# LiFePo4_Charger_Single_to_Chain_2_1_SMD_.net
KiCad netlist of a schematic drawn in EAGLE
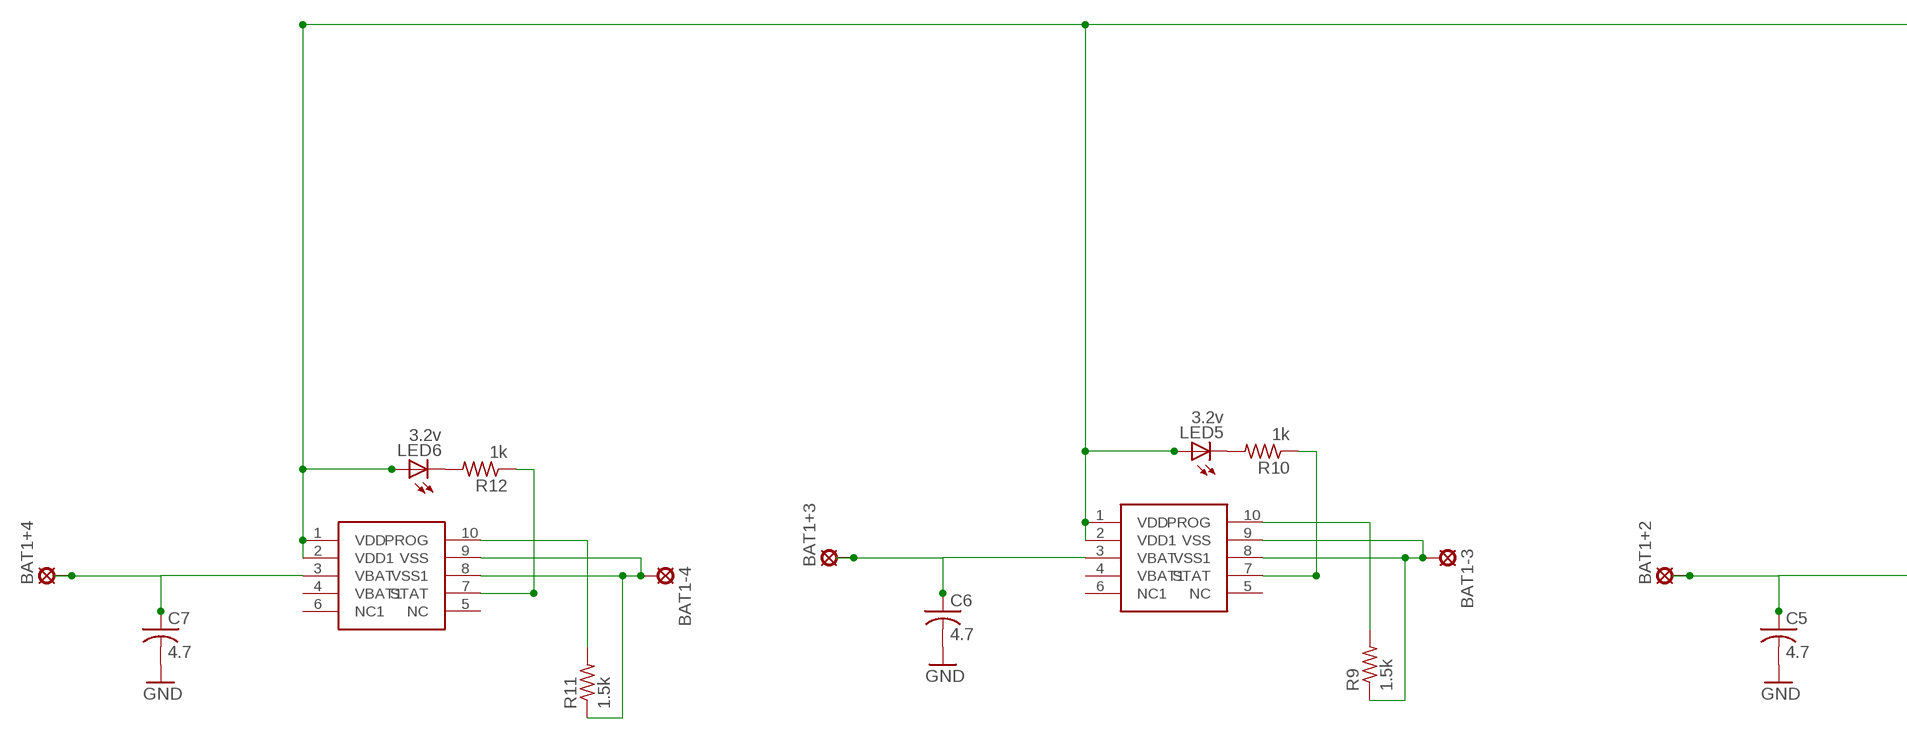
[diagram p0: schematic, sheet 1, part 1 of 2]
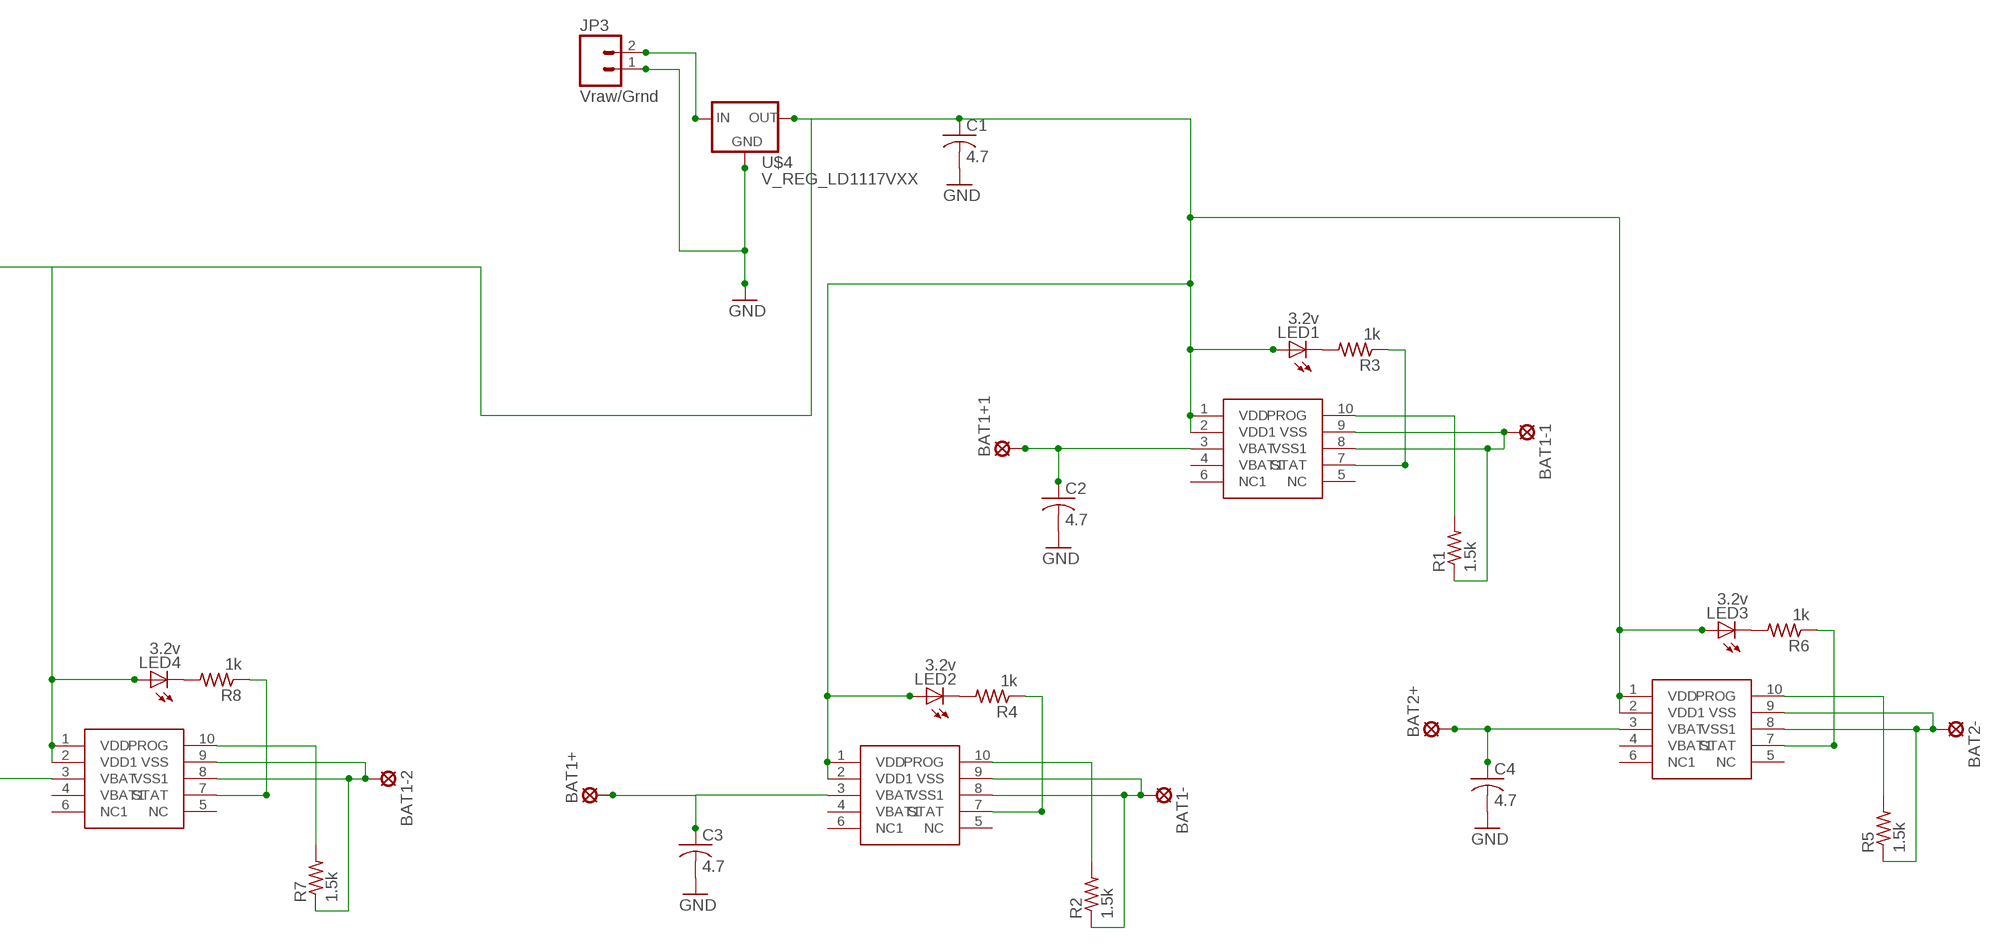
[diagram p1: schematic, sheet 1, part 2 of 2]

(export (version "E")
  (design (tool "Eeschema 10.0.6"))
  (components
    (comp (ref "BAT1+")
      (value "SE14")
      (footprint "eagle-import:SE14")
      (libsource (lib "eagle-import") (part "SE14"))
    )
    (comp (ref "BAT1+1")
      (value "SE14")
      (footprint "eagle-import:SE14")
      (libsource (lib "eagle-import") (part "SE14"))
    )
    (comp (ref "BAT1+2")
      (value "SE14")
      (footprint "eagle-import:SE14")
      (libsource (lib "eagle-import") (part "SE14"))
    )
    (comp (ref "BAT1+3")
      (value "SE14")
      (footprint "eagle-import:SE14")
      (libsource (lib "eagle-import") (part "SE14"))
    )
    (comp (ref "BAT1+4")
      (value "SE14")
      (footprint "eagle-import:SE14")
      (libsource (lib "eagle-import") (part "SE14"))
    )
    (comp (ref "BAT1-")
      (value "SE14")
      (footprint "eagle-import:SE14")
      (libsource (lib "eagle-import") (part "SE14"))
    )
    (comp (ref "BAT1-1")
      (value "SE14")
      (footprint "eagle-import:SE14")
      (libsource (lib "eagle-import") (part "SE14"))
    )
    (comp (ref "BAT1-2")
      (value "SE14")
      (footprint "eagle-import:SE14")
      (libsource (lib "eagle-import") (part "SE14"))
    )
    (comp (ref "BAT1-3")
      (value "SE14")
      (footprint "eagle-import:SE14")
      (libsource (lib "eagle-import") (part "SE14"))
    )
    (comp (ref "BAT1-4")
      (value "SE14")
      (footprint "eagle-import:SE14")
      (libsource (lib "eagle-import") (part "SE14"))
    )
    (comp (ref "BAT2+")
      (value "SE14")
      (footprint "eagle-import:SE14")
      (libsource (lib "eagle-import") (part "SE14"))
    )
    (comp (ref "BAT2-")
      (value "SE14")
      (footprint "eagle-import:SE14")
      (libsource (lib "eagle-import") (part "SE14"))
    )
    (comp (ref "C1")
      (value "4.7")
      (footprint "eagle-import:C0805")
      (libsource (lib "eagle-import") (part "C-USC0805"))
    )
    (comp (ref "C2")
      (value "4.7")
      (footprint "eagle-import:C0805")
      (libsource (lib "eagle-import") (part "C-USC0805"))
    )
    (comp (ref "C3")
      (value "4.7")
      (footprint "eagle-import:C0805")
      (libsource (lib "eagle-import") (part "C-USC0805"))
    )
    (comp (ref "C4")
      (value "4.7")
      (footprint "eagle-import:C0805")
      (libsource (lib "eagle-import") (part "C-USC0805"))
    )
    (comp (ref "C5")
      (value "4.7")
      (footprint "eagle-import:C0805")
      (libsource (lib "eagle-import") (part "C-USC0805"))
    )
    (comp (ref "C6")
      (value "4.7")
      (footprint "eagle-import:C0805")
      (libsource (lib "eagle-import") (part "C-USC0805"))
    )
    (comp (ref "C7")
      (value "4.7")
      (footprint "eagle-import:C0805")
      (libsource (lib "eagle-import") (part "C-USC0805"))
    )
    (comp (ref "JP3")
      (value "Vraw/Grnd")
      (footprint "eagle-import:1X02")
      (libsource (lib "eagle-import") (part "M02PTH"))
    )
    (comp (ref "LED1")
      (value "3.2v")
      (footprint "eagle-import:SML0603")
      (libsource (lib "eagle-import") (part "LEDSML0603"))
    )
    (comp (ref "LED2")
      (value "3.2v")
      (footprint "eagle-import:SML0603")
      (libsource (lib "eagle-import") (part "LEDSML0603"))
    )
    (comp (ref "LED3")
      (value "3.2v")
      (footprint "eagle-import:SML0603")
      (libsource (lib "eagle-import") (part "LEDSML0603"))
    )
    (comp (ref "LED4")
      (value "3.2v")
      (footprint "eagle-import:SML0603")
      (libsource (lib "eagle-import") (part "LEDSML0603"))
    )
    (comp (ref "LED5")
      (value "3.2v")
      (footprint "eagle-import:SML0603")
      (libsource (lib "eagle-import") (part "LEDSML0603"))
    )
    (comp (ref "LED6")
      (value "3.2v")
      (footprint "eagle-import:SML0603")
      (libsource (lib "eagle-import") (part "LEDSML0603"))
    )
    (comp (ref "R1")
      (value "1.5k")
      (footprint "eagle-import:R0805")
      (libsource (lib "eagle-import") (part "R-US_R0805"))
    )
    (comp (ref "R2")
      (value "1.5k")
      (footprint "eagle-import:R0805")
      (libsource (lib "eagle-import") (part "R-US_R0805"))
    )
    (comp (ref "R3")
      (value "1k")
      (footprint "eagle-import:R0805")
      (libsource (lib "eagle-import") (part "R-US_R0805"))
    )
    (comp (ref "R4")
      (value "1k")
      (footprint "eagle-import:R0805")
      (libsource (lib "eagle-import") (part "R-US_R0805"))
    )
    (comp (ref "R5")
      (value "1.5k")
      (footprint "eagle-import:R0805")
      (libsource (lib "eagle-import") (part "R-US_R0805"))
    )
    (comp (ref "R6")
      (value "1k")
      (footprint "eagle-import:R0805")
      (libsource (lib "eagle-import") (part "R-US_R0805"))
    )
    (comp (ref "R7")
      (value "1.5k")
      (footprint "eagle-import:R0805")
      (libsource (lib "eagle-import") (part "R-US_R0805"))
    )
    (comp (ref "R8")
      (value "1k")
      (footprint "eagle-import:R0805")
      (libsource (lib "eagle-import") (part "R-US_R0805"))
    )
    (comp (ref "R9")
      (value "1.5k")
      (footprint "eagle-import:R0805")
      (libsource (lib "eagle-import") (part "R-US_R0805"))
    )
    (comp (ref "R10")
      (value "1k")
      (footprint "eagle-import:R0805")
      (libsource (lib "eagle-import") (part "R-US_R0805"))
    )
    (comp (ref "R11")
      (value "1.5k")
      (footprint "eagle-import:R0805")
      (libsource (lib "eagle-import") (part "R-US_R0805"))
    )
    (comp (ref "R12")
      (value "1k")
      (footprint "eagle-import:R0805")
      (libsource (lib "eagle-import") (part "R-US_R0805"))
    )
    (comp (ref "U$1")
      (value "MCP73123/223")
      (footprint "eagle-import:MCP73123_223")
      (libsource (lib "eagle-import") (part "MCP73123/223"))
    )
    (comp (ref "U$2")
      (value "MCP73123/223")
      (footprint "eagle-import:MCP73123_223")
      (libsource (lib "eagle-import") (part "MCP73123/223"))
    )
    (comp (ref "U$3")
      (value "MCP73123/223")
      (footprint "eagle-import:MCP73123_223")
      (libsource (lib "eagle-import") (part "MCP73123/223"))
    )
    (comp (ref "U$4")
      (value "V_REG_LD1117VXX")
      (footprint "eagle-import:78XXL")
      (libsource (lib "eagle-import") (part "V_REG_LD1117VXX"))
    )
    (comp (ref "U$5")
      (value "MCP73123/223")
      (footprint "eagle-import:MCP73123_223")
      (libsource (lib "eagle-import") (part "MCP73123/223"))
    )
    (comp (ref "U$6")
      (value "MCP73123/223")
      (footprint "eagle-import:MCP73123_223")
      (libsource (lib "eagle-import") (part "MCP73123/223"))
    )
    (comp (ref "U$8")
      (value "MCP73123/223")
      (footprint "eagle-import:MCP73123_223")
      (libsource (lib "eagle-import") (part "MCP73123/223"))
    )
  )
  (nets
    (net (code "1") (name "GND") (class "Default")
      (node (ref "C1") (pin "2") (pinfunction "2_2") (pintype "passive"))
      (node (ref "C2") (pin "2") (pinfunction "2_2") (pintype "passive"))
      (node (ref "C3") (pin "2") (pinfunction "2_2") (pintype "passive"))
      (node (ref "C4") (pin "2") (pinfunction "2_2") (pintype "passive"))
      (node (ref "C5") (pin "2") (pinfunction "2_2") (pintype "passive"))
      (node (ref "C6") (pin "2") (pinfunction "2_2") (pintype "passive"))
      (node (ref "C7") (pin "2") (pinfunction "2_2") (pintype "passive"))
      (node (ref "JP3") (pin "1") (pinfunction "1_1") (pintype "passive"))
      (node (ref "U$4") (pin "IN") (pinfunction "GND_IN") (pintype "input"))
    )
    (net (code "2") (name "Net-(LED1-PadC)") (class "Default")
      (node (ref "LED1") (pin "C") (pinfunction "C_C") (pintype "passive"))
      (node (ref "R3") (pin "2") (pinfunction "2_2") (pintype "passive"))
    )
    (net (code "3") (name "Net-(LED2-PadC)") (class "Default")
      (node (ref "LED2") (pin "C") (pinfunction "C_C") (pintype "passive"))
      (node (ref "R4") (pin "2") (pinfunction "2_2") (pintype "passive"))
    )
    (net (code "4") (name "Net-(LED3-PadC)") (class "Default")
      (node (ref "LED3") (pin "C") (pinfunction "C_C") (pintype "passive"))
      (node (ref "R6") (pin "2") (pinfunction "2_2") (pintype "passive"))
    )
    (net (code "5") (name "Net-(LED4-PadC)") (class "Default")
      (node (ref "LED4") (pin "C") (pinfunction "C_C") (pintype "passive"))
      (node (ref "R8") (pin "2") (pinfunction "2_2") (pintype "passive"))
    )
    (net (code "6") (name "Net-(LED5-PadC)") (class "Default")
      (node (ref "LED5") (pin "C") (pinfunction "C_C") (pintype "passive"))
      (node (ref "R10") (pin "2") (pinfunction "2_2") (pintype "passive"))
    )
    (net (code "7") (name "Net-(LED6-PadC)") (class "Default")
      (node (ref "LED6") (pin "C") (pinfunction "C_C") (pintype "passive"))
      (node (ref "R12") (pin "2") (pinfunction "2_2") (pintype "passive"))
    )
    (net (code "8") (name "Net-(U$1-PROG)") (class "Default")
      (node (ref "R2") (pin "2") (pinfunction "2_2") (pintype "passive"))
      (node (ref "U$1") (pin "10") (pinfunction "PROG_10") (pintype "bidirectional"))
    )
    (net (code "9") (name "Net-(U$1-STAT)") (class "Default")
      (node (ref "R4") (pin "1") (pinfunction "1_1") (pintype "passive"))
      (node (ref "U$1") (pin "7") (pinfunction "STAT_7") (pintype "bidirectional"))
    )
    (net (code "10") (name "Net-(U$1-VBAT)") (class "Default")
      (node (ref "BAT1+") (pin "MP") (pinfunction "MP_MP") (pintype "passive"))
      (node (ref "C3") (pin "1") (pinfunction "1_1") (pintype "passive"))
      (node (ref "U$1") (pin "3") (pinfunction "VBAT_3") (pintype "bidirectional"))
    )
    (net (code "11") (name "Net-(U$1-VDD)") (class "Default")
      (node (ref "C1") (pin "1") (pinfunction "1_1") (pintype "passive"))
      (node (ref "LED1") (pin "A") (pinfunction "A_A") (pintype "passive"))
      (node (ref "LED2") (pin "A") (pinfunction "A_A") (pintype "passive"))
      (node (ref "LED3") (pin "A") (pinfunction "A_A") (pintype "passive"))
      (node (ref "LED5") (pin "A") (pinfunction "A_A") (pintype "passive"))
      (node (ref "LED6") (pin "A") (pinfunction "A_A") (pintype "passive"))
      (node (ref "U$1") (pin "1") (pinfunction "VDD_1") (pintype "bidirectional"))
      (node (ref "U$1") (pin "2") (pinfunction "VDD1_2") (pintype "bidirectional"))
      (node (ref "U$2") (pin "1") (pinfunction "VDD_1") (pintype "bidirectional"))
      (node (ref "U$2") (pin "2") (pinfunction "VDD1_2") (pintype "bidirectional"))
      (node (ref "U$4") (pin "GND") (pinfunction "OUT_GND") (pintype "output"))
      (node (ref "U$5") (pin "1") (pinfunction "VDD_1") (pintype "bidirectional"))
      (node (ref "U$5") (pin "2") (pinfunction "VDD1_2") (pintype "bidirectional"))
      (node (ref "U$6") (pin "1") (pinfunction "VDD_1") (pintype "bidirectional"))
      (node (ref "U$6") (pin "2") (pinfunction "VDD1_2") (pintype "bidirectional"))
      (node (ref "U$8") (pin "1") (pinfunction "VDD_1") (pintype "bidirectional"))
      (node (ref "U$8") (pin "2") (pinfunction "VDD1_2") (pintype "bidirectional"))
    )
    (net (code "12") (name "Net-(U$1-VSS)") (class "Default")
      (node (ref "BAT1-") (pin "MP") (pinfunction "MP_MP") (pintype "passive"))
      (node (ref "R2") (pin "1") (pinfunction "1_1") (pintype "passive"))
      (node (ref "U$1") (pin "8") (pinfunction "VSS1_8") (pintype "bidirectional"))
      (node (ref "U$1") (pin "9") (pinfunction "VSS_9") (pintype "bidirectional"))
    )
    (net (code "13") (name "Net-(U$2-PROG)") (class "Default")
      (node (ref "R5") (pin "2") (pinfunction "2_2") (pintype "passive"))
      (node (ref "U$2") (pin "10") (pinfunction "PROG_10") (pintype "bidirectional"))
    )
    (net (code "14") (name "Net-(U$2-STAT)") (class "Default")
      (node (ref "R6") (pin "1") (pinfunction "1_1") (pintype "passive"))
      (node (ref "U$2") (pin "7") (pinfunction "STAT_7") (pintype "bidirectional"))
    )
    (net (code "15") (name "Net-(U$2-VBAT)") (class "Default")
      (node (ref "BAT2+") (pin "MP") (pinfunction "MP_MP") (pintype "passive"))
      (node (ref "C4") (pin "1") (pinfunction "1_1") (pintype "passive"))
      (node (ref "U$2") (pin "3") (pinfunction "VBAT_3") (pintype "bidirectional"))
    )
    (net (code "16") (name "Net-(U$2-VSS)") (class "Default")
      (node (ref "BAT2-") (pin "MP") (pinfunction "MP_MP") (pintype "passive"))
      (node (ref "R5") (pin "1") (pinfunction "1_1") (pintype "passive"))
      (node (ref "U$2") (pin "8") (pinfunction "VSS1_8") (pintype "bidirectional"))
      (node (ref "U$2") (pin "9") (pinfunction "VSS_9") (pintype "bidirectional"))
    )
    (net (code "17") (name "Net-(U$3-PROG)") (class "Default")
      (node (ref "R7") (pin "2") (pinfunction "2_2") (pintype "passive"))
      (node (ref "U$3") (pin "10") (pinfunction "PROG_10") (pintype "bidirectional"))
    )
    (net (code "18") (name "Net-(U$3-STAT)") (class "Default")
      (node (ref "R8") (pin "1") (pinfunction "1_1") (pintype "passive"))
      (node (ref "U$3") (pin "7") (pinfunction "STAT_7") (pintype "bidirectional"))
    )
    (net (code "19") (name "Net-(U$3-VBAT)") (class "Default")
      (node (ref "BAT1+2") (pin "MP") (pinfunction "MP_MP") (pintype "passive"))
      (node (ref "C5") (pin "1") (pinfunction "1_1") (pintype "passive"))
      (node (ref "U$3") (pin "3") (pinfunction "VBAT_3") (pintype "bidirectional"))
    )
    (net (code "20") (name "Net-(U$3-VDD)") (class "Default")
      (node (ref "LED4") (pin "A") (pinfunction "A_A") (pintype "passive"))
      (node (ref "U$3") (pin "1") (pinfunction "VDD_1") (pintype "bidirectional"))
      (node (ref "U$3") (pin "2") (pinfunction "VDD1_2") (pintype "bidirectional"))
    )
    (net (code "21") (name "Net-(U$3-VSS)") (class "Default")
      (node (ref "BAT1-2") (pin "MP") (pinfunction "MP_MP") (pintype "passive"))
      (node (ref "R7") (pin "1") (pinfunction "1_1") (pintype "passive"))
      (node (ref "U$3") (pin "8") (pinfunction "VSS1_8") (pintype "bidirectional"))
      (node (ref "U$3") (pin "9") (pinfunction "VSS_9") (pintype "bidirectional"))
    )
    (net (code "22") (name "Net-(U$4-IN)") (class "Default")
      (node (ref "JP3") (pin "2") (pinfunction "2_2") (pintype "passive"))
      (node (ref "U$4") (pin "OUT") (pinfunction "IN_OUT") (pintype "input"))
    )
    (net (code "23") (name "Net-(U$5-PROG)") (class "Default")
      (node (ref "R9") (pin "2") (pinfunction "2_2") (pintype "passive"))
      (node (ref "U$5") (pin "10") (pinfunction "PROG_10") (pintype "bidirectional"))
    )
    (net (code "24") (name "Net-(U$5-STAT)") (class "Default")
      (node (ref "R10") (pin "1") (pinfunction "1_1") (pintype "passive"))
      (node (ref "U$5") (pin "7") (pinfunction "STAT_7") (pintype "bidirectional"))
    )
    (net (code "25") (name "Net-(U$5-VBAT)") (class "Default")
      (node (ref "BAT1+3") (pin "MP") (pinfunction "MP_MP") (pintype "passive"))
      (node (ref "C6") (pin "1") (pinfunction "1_1") (pintype "passive"))
      (node (ref "U$5") (pin "3") (pinfunction "VBAT_3") (pintype "bidirectional"))
    )
    (net (code "26") (name "Net-(U$5-VSS)") (class "Default")
      (node (ref "BAT1-3") (pin "MP") (pinfunction "MP_MP") (pintype "passive"))
      (node (ref "R9") (pin "1") (pinfunction "1_1") (pintype "passive"))
      (node (ref "U$5") (pin "8") (pinfunction "VSS1_8") (pintype "bidirectional"))
      (node (ref "U$5") (pin "9") (pinfunction "VSS_9") (pintype "bidirectional"))
    )
    (net (code "27") (name "Net-(U$6-PROG)") (class "Default")
      (node (ref "R11") (pin "2") (pinfunction "2_2") (pintype "passive"))
      (node (ref "U$6") (pin "10") (pinfunction "PROG_10") (pintype "bidirectional"))
    )
    (net (code "28") (name "Net-(U$6-STAT)") (class "Default")
      (node (ref "R12") (pin "1") (pinfunction "1_1") (pintype "passive"))
      (node (ref "U$6") (pin "7") (pinfunction "STAT_7") (pintype "bidirectional"))
    )
    (net (code "29") (name "Net-(U$6-VBAT)") (class "Default")
      (node (ref "BAT1+4") (pin "MP") (pinfunction "MP_MP") (pintype "passive"))
      (node (ref "C7") (pin "1") (pinfunction "1_1") (pintype "passive"))
      (node (ref "U$6") (pin "3") (pinfunction "VBAT_3") (pintype "bidirectional"))
    )
    (net (code "30") (name "Net-(U$6-VSS)") (class "Default")
      (node (ref "BAT1-4") (pin "MP") (pinfunction "MP_MP") (pintype "passive"))
      (node (ref "R11") (pin "1") (pinfunction "1_1") (pintype "passive"))
      (node (ref "U$6") (pin "8") (pinfunction "VSS1_8") (pintype "bidirectional"))
      (node (ref "U$6") (pin "9") (pinfunction "VSS_9") (pintype "bidirectional"))
    )
    (net (code "31") (name "Net-(U$8-PROG)") (class "Default")
      (node (ref "R1") (pin "2") (pinfunction "2_2") (pintype "passive"))
      (node (ref "U$8") (pin "10") (pinfunction "PROG_10") (pintype "bidirectional"))
    )
    (net (code "32") (name "Net-(U$8-STAT)") (class "Default")
      (node (ref "R3") (pin "1") (pinfunction "1_1") (pintype "passive"))
      (node (ref "U$8") (pin "7") (pinfunction "STAT_7") (pintype "bidirectional"))
    )
    (net (code "33") (name "Net-(U$8-VBAT)") (class "Default")
      (node (ref "BAT1+1") (pin "MP") (pinfunction "MP_MP") (pintype "passive"))
      (node (ref "C2") (pin "1") (pinfunction "1_1") (pintype "passive"))
      (node (ref "U$8") (pin "3") (pinfunction "VBAT_3") (pintype "bidirectional"))
    )
    (net (code "34") (name "Net-(U$8-VSS)") (class "Default")
      (node (ref "BAT1-1") (pin "MP") (pinfunction "MP_MP") (pintype "passive"))
      (node (ref "R1") (pin "1") (pinfunction "1_1") (pintype "passive"))
      (node (ref "U$8") (pin "8") (pinfunction "VSS1_8") (pintype "bidirectional"))
      (node (ref "U$8") (pin "9") (pinfunction "VSS_9") (pintype "bidirectional"))
    )
    (net (code "35") (name "unconnected-(U$1-NC-Pad5)") (class "Default")
      (node (ref "U$1") (pin "5") (pinfunction "NC_5") (pintype "bidirectional"))
    )
    (net (code "36") (name "unconnected-(U$1-NC1-Pad6)") (class "Default")
      (node (ref "U$1") (pin "6") (pinfunction "NC1_6") (pintype "bidirectional"))
    )
    (net (code "37") (name "unconnected-(U$1-VBAT1-Pad4)") (class "Default")
      (node (ref "U$1") (pin "4") (pinfunction "VBAT1_4") (pintype "bidirectional"))
    )
    (net (code "38") (name "unconnected-(U$2-NC-Pad5)") (class "Default")
      (node (ref "U$2") (pin "5") (pinfunction "NC_5") (pintype "bidirectional"))
    )
    (net (code "39") (name "unconnected-(U$2-NC1-Pad6)") (class "Default")
      (node (ref "U$2") (pin "6") (pinfunction "NC1_6") (pintype "bidirectional"))
    )
    (net (code "40") (name "unconnected-(U$2-VBAT1-Pad4)") (class "Default")
      (node (ref "U$2") (pin "4") (pinfunction "VBAT1_4") (pintype "bidirectional"))
    )
    (net (code "41") (name "unconnected-(U$3-NC-Pad5)") (class "Default")
      (node (ref "U$3") (pin "5") (pinfunction "NC_5") (pintype "bidirectional"))
    )
    (net (code "42") (name "unconnected-(U$3-NC1-Pad6)") (class "Default")
      (node (ref "U$3") (pin "6") (pinfunction "NC1_6") (pintype "bidirectional"))
    )
    (net (code "43") (name "unconnected-(U$3-VBAT1-Pad4)") (class "Default")
      (node (ref "U$3") (pin "4") (pinfunction "VBAT1_4") (pintype "bidirectional"))
    )
    (net (code "44") (name "unconnected-(U$5-NC-Pad5)") (class "Default")
      (node (ref "U$5") (pin "5") (pinfunction "NC_5") (pintype "bidirectional"))
    )
    (net (code "45") (name "unconnected-(U$5-NC1-Pad6)") (class "Default")
      (node (ref "U$5") (pin "6") (pinfunction "NC1_6") (pintype "bidirectional"))
    )
    (net (code "46") (name "unconnected-(U$5-VBAT1-Pad4)") (class "Default")
      (node (ref "U$5") (pin "4") (pinfunction "VBAT1_4") (pintype "bidirectional"))
    )
    (net (code "47") (name "unconnected-(U$6-NC-Pad5)") (class "Default")
      (node (ref "U$6") (pin "5") (pinfunction "NC_5") (pintype "bidirectional"))
    )
    (net (code "48") (name "unconnected-(U$6-NC1-Pad6)") (class "Default")
      (node (ref "U$6") (pin "6") (pinfunction "NC1_6") (pintype "bidirectional"))
    )
    (net (code "49") (name "unconnected-(U$6-VBAT1-Pad4)") (class "Default")
      (node (ref "U$6") (pin "4") (pinfunction "VBAT1_4") (pintype "bidirectional"))
    )
    (net (code "50") (name "unconnected-(U$8-NC-Pad5)") (class "Default")
      (node (ref "U$8") (pin "5") (pinfunction "NC_5") (pintype "bidirectional"))
    )
    (net (code "51") (name "unconnected-(U$8-NC1-Pad6)") (class "Default")
      (node (ref "U$8") (pin "6") (pinfunction "NC1_6") (pintype "bidirectional"))
    )
    (net (code "52") (name "unconnected-(U$8-VBAT1-Pad4)") (class "Default")
      (node (ref "U$8") (pin "4") (pinfunction "VBAT1_4") (pintype "bidirectional"))
    )
  )
)
